# w.net
KiCad netlist of a schematic drawn in EAGLE
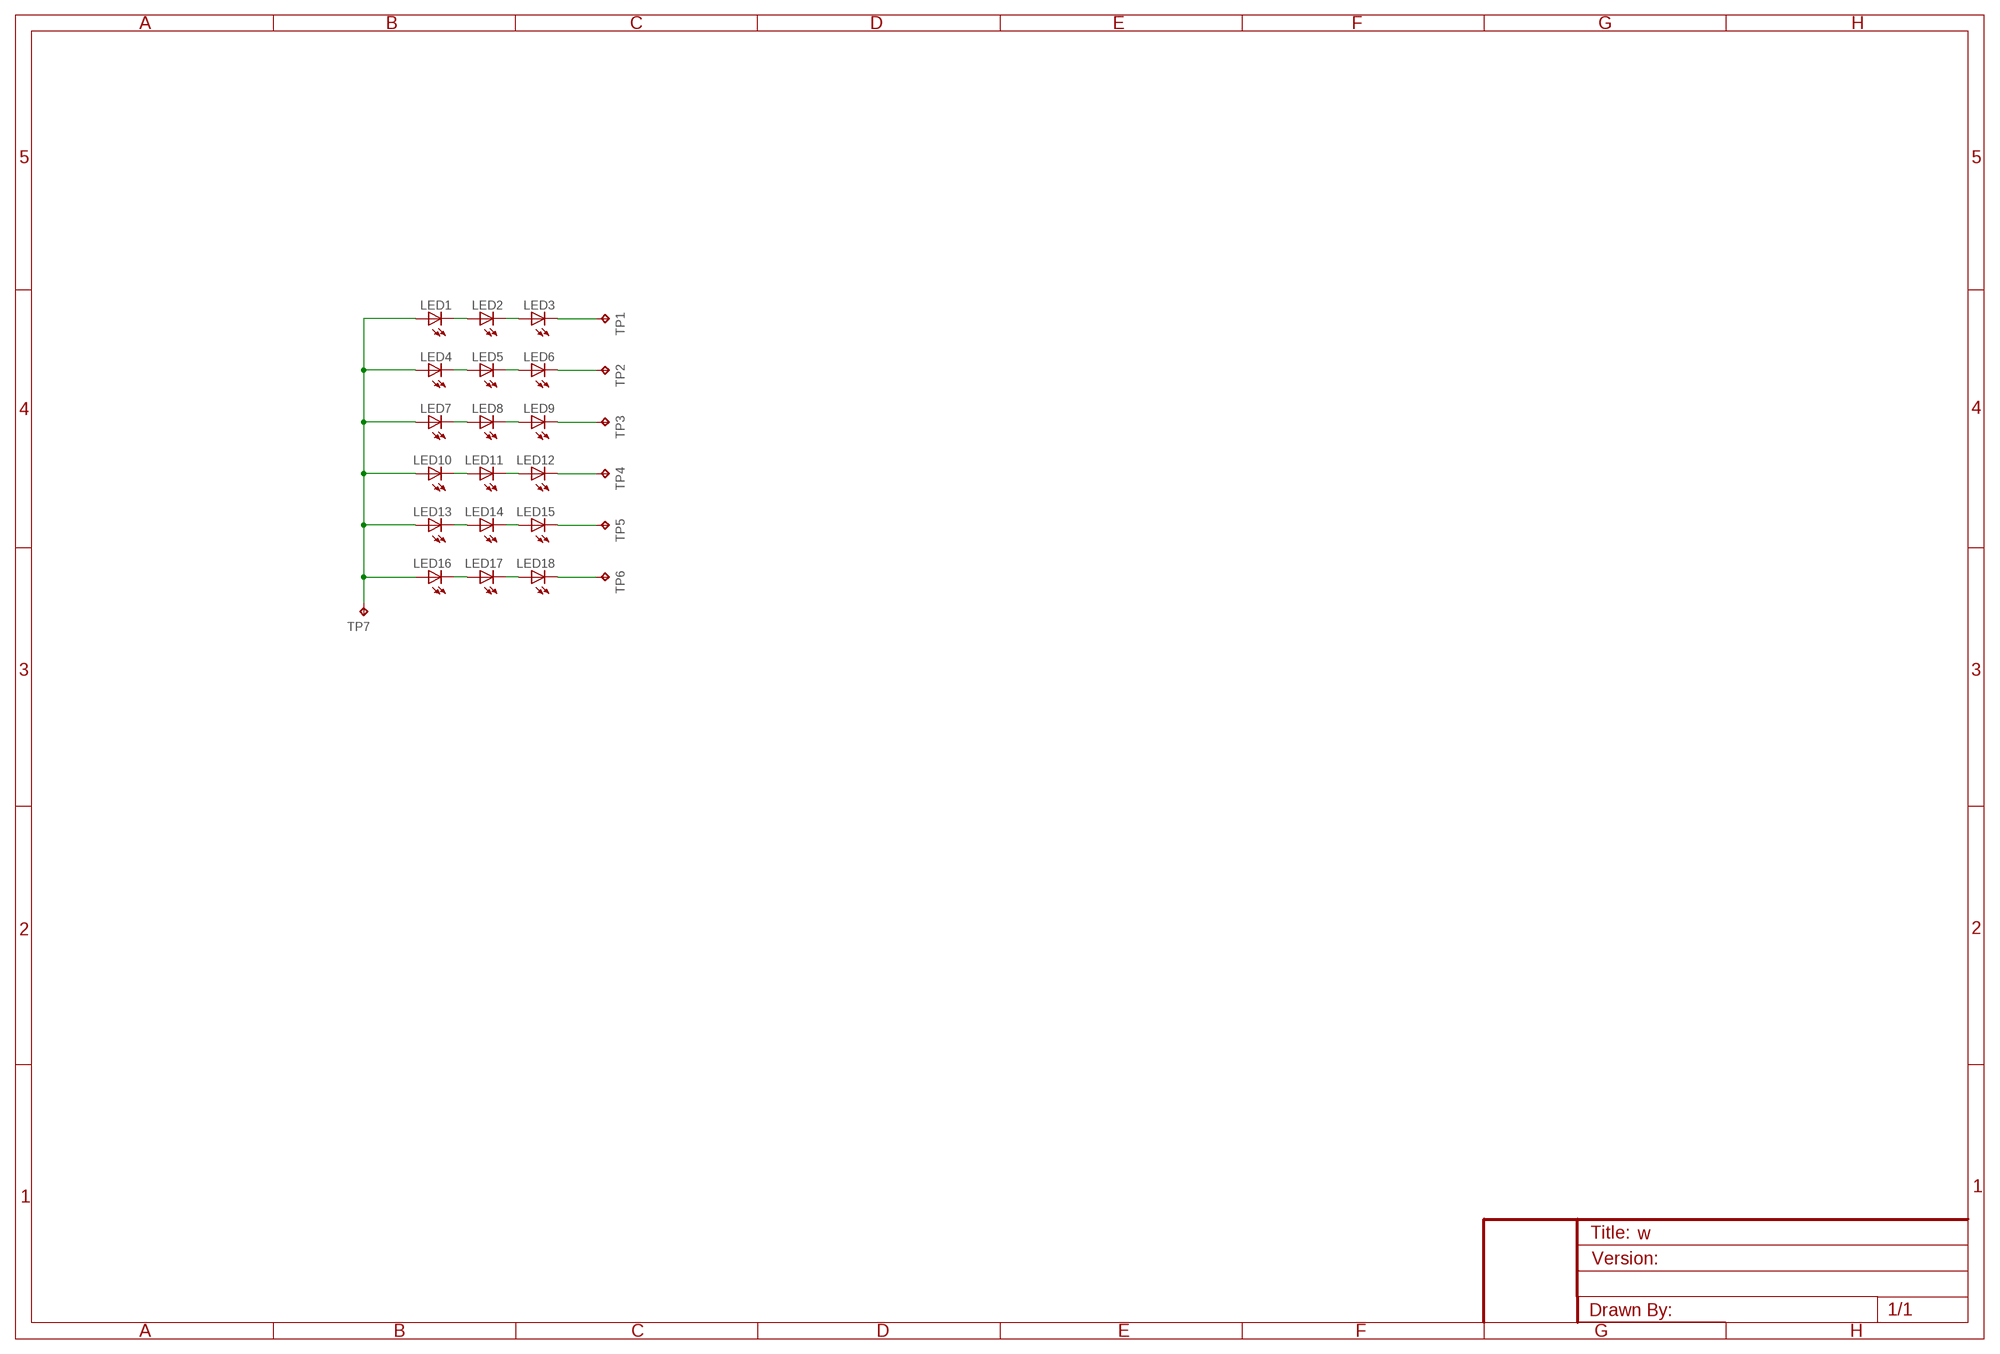
[diagram p0: schematic, sheet 1]

(export (version "E")
  (design (tool "Eeschema 10.0.6"))
  (components
    (comp (ref "LED1")
      (value "LED0805")
      (footprint "eagle-import:LED_0805")
      (libsource (lib "eagle-import") (part "LED0805"))
    )
    (comp (ref "LED2")
      (value "LED0805")
      (footprint "eagle-import:LED_0805")
      (libsource (lib "eagle-import") (part "LED0805"))
    )
    (comp (ref "LED3")
      (value "LED0805")
      (footprint "eagle-import:LED_0805")
      (libsource (lib "eagle-import") (part "LED0805"))
    )
    (comp (ref "LED4")
      (value "LED0805")
      (footprint "eagle-import:LED_0805")
      (libsource (lib "eagle-import") (part "LED0805"))
    )
    (comp (ref "LED5")
      (value "LED0805")
      (footprint "eagle-import:LED_0805")
      (libsource (lib "eagle-import") (part "LED0805"))
    )
    (comp (ref "LED6")
      (value "LED0805")
      (footprint "eagle-import:LED_0805")
      (libsource (lib "eagle-import") (part "LED0805"))
    )
    (comp (ref "LED7")
      (value "LED0805")
      (footprint "eagle-import:LED_0805")
      (libsource (lib "eagle-import") (part "LED0805"))
    )
    (comp (ref "LED8")
      (value "LED0805")
      (footprint "eagle-import:LED_0805")
      (libsource (lib "eagle-import") (part "LED0805"))
    )
    (comp (ref "LED9")
      (value "LED0805")
      (footprint "eagle-import:LED_0805")
      (libsource (lib "eagle-import") (part "LED0805"))
    )
    (comp (ref "LED10")
      (value "LED0805")
      (footprint "eagle-import:LED_0805")
      (libsource (lib "eagle-import") (part "LED0805"))
    )
    (comp (ref "LED11")
      (value "LED0805")
      (footprint "eagle-import:LED_0805")
      (libsource (lib "eagle-import") (part "LED0805"))
    )
    (comp (ref "LED12")
      (value "LED0805")
      (footprint "eagle-import:LED_0805")
      (libsource (lib "eagle-import") (part "LED0805"))
    )
    (comp (ref "LED13")
      (value "LED0805")
      (footprint "eagle-import:LED_0805")
      (libsource (lib "eagle-import") (part "LED0805"))
    )
    (comp (ref "LED14")
      (value "LED0805")
      (footprint "eagle-import:LED_0805")
      (libsource (lib "eagle-import") (part "LED0805"))
    )
    (comp (ref "LED15")
      (value "LED0805")
      (footprint "eagle-import:LED_0805")
      (libsource (lib "eagle-import") (part "LED0805"))
    )
    (comp (ref "LED16")
      (value "LED0805")
      (footprint "eagle-import:LED_0805")
      (libsource (lib "eagle-import") (part "LED0805"))
    )
    (comp (ref "LED17")
      (value "LED0805")
      (footprint "eagle-import:LED_0805")
      (libsource (lib "eagle-import") (part "LED0805"))
    )
    (comp (ref "LED18")
      (value "LED0805")
      (footprint "eagle-import:LED_0805")
      (libsource (lib "eagle-import") (part "LED0805"))
    )
    (comp (ref "TP1")
      (value "TEST_POINTPAD1-20")
      (footprint "eagle-import:P1-20")
      (libsource (lib "eagle-import") (part "TEST_POINTPAD1-20"))
    )
    (comp (ref "TP2")
      (value "TEST_POINTPAD1-20")
      (footprint "eagle-import:P1-20")
      (libsource (lib "eagle-import") (part "TEST_POINTPAD1-20"))
    )
    (comp (ref "TP3")
      (value "TEST_POINTPAD1-20")
      (footprint "eagle-import:P1-20")
      (libsource (lib "eagle-import") (part "TEST_POINTPAD1-20"))
    )
    (comp (ref "TP4")
      (value "TEST_POINTPAD1-20")
      (footprint "eagle-import:P1-20")
      (libsource (lib "eagle-import") (part "TEST_POINTPAD1-20"))
    )
    (comp (ref "TP5")
      (value "TEST_POINTPAD1-20")
      (footprint "eagle-import:P1-20")
      (libsource (lib "eagle-import") (part "TEST_POINTPAD1-20"))
    )
    (comp (ref "TP6")
      (value "TEST_POINTPAD1-20")
      (footprint "eagle-import:P1-20")
      (libsource (lib "eagle-import") (part "TEST_POINTPAD1-20"))
    )
    (comp (ref "TP7")
      (value "TEST_POINTPAD1-20")
      (footprint "eagle-import:P1-20")
      (libsource (lib "eagle-import") (part "TEST_POINTPAD1-20"))
    )
  )
  (nets
    (net (code "1") (name "Net-(LED1-PadA)") (class "Default")
      (node (ref "LED1") (pin "A") (pinfunction "A_A") (pintype "passive"))
      (node (ref "LED10") (pin "A") (pinfunction "A_A") (pintype "passive"))
      (node (ref "LED13") (pin "A") (pinfunction "A_A") (pintype "passive"))
      (node (ref "LED16") (pin "A") (pinfunction "A_A") (pintype "passive"))
      (node (ref "LED4") (pin "A") (pinfunction "A_A") (pintype "passive"))
      (node (ref "LED7") (pin "A") (pinfunction "A_A") (pintype "passive"))
      (node (ref "TP7") (pin "TP") (pinfunction "TP_TP") (pintype "input"))
    )
    (net (code "2") (name "Net-(LED1-PadC)") (class "Default")
      (node (ref "LED1") (pin "C") (pinfunction "C_C") (pintype "passive"))
      (node (ref "LED2") (pin "A") (pinfunction "A_A") (pintype "passive"))
    )
    (net (code "3") (name "Net-(LED2-PadC)") (class "Default")
      (node (ref "LED2") (pin "C") (pinfunction "C_C") (pintype "passive"))
      (node (ref "LED3") (pin "A") (pinfunction "A_A") (pintype "passive"))
    )
    (net (code "4") (name "Net-(LED3-PadC)") (class "Default")
      (node (ref "LED3") (pin "C") (pinfunction "C_C") (pintype "passive"))
      (node (ref "TP1") (pin "TP") (pinfunction "TP_TP") (pintype "input"))
    )
    (net (code "5") (name "Net-(LED4-PadC)") (class "Default")
      (node (ref "LED4") (pin "C") (pinfunction "C_C") (pintype "passive"))
      (node (ref "LED5") (pin "A") (pinfunction "A_A") (pintype "passive"))
    )
    (net (code "6") (name "Net-(LED5-PadC)") (class "Default")
      (node (ref "LED5") (pin "C") (pinfunction "C_C") (pintype "passive"))
      (node (ref "LED6") (pin "A") (pinfunction "A_A") (pintype "passive"))
    )
    (net (code "7") (name "Net-(LED6-PadC)") (class "Default")
      (node (ref "LED6") (pin "C") (pinfunction "C_C") (pintype "passive"))
      (node (ref "TP2") (pin "TP") (pinfunction "TP_TP") (pintype "input"))
    )
    (net (code "8") (name "Net-(LED7-PadC)") (class "Default")
      (node (ref "LED7") (pin "C") (pinfunction "C_C") (pintype "passive"))
      (node (ref "LED8") (pin "A") (pinfunction "A_A") (pintype "passive"))
    )
    (net (code "9") (name "Net-(LED8-PadC)") (class "Default")
      (node (ref "LED8") (pin "C") (pinfunction "C_C") (pintype "passive"))
      (node (ref "LED9") (pin "A") (pinfunction "A_A") (pintype "passive"))
    )
    (net (code "10") (name "Net-(LED9-PadC)") (class "Default")
      (node (ref "LED9") (pin "C") (pinfunction "C_C") (pintype "passive"))
      (node (ref "TP3") (pin "TP") (pinfunction "TP_TP") (pintype "input"))
    )
    (net (code "11") (name "Net-(LED10-PadC)") (class "Default")
      (node (ref "LED10") (pin "C") (pinfunction "C_C") (pintype "passive"))
      (node (ref "LED11") (pin "A") (pinfunction "A_A") (pintype "passive"))
    )
    (net (code "12") (name "Net-(LED11-PadC)") (class "Default")
      (node (ref "LED11") (pin "C") (pinfunction "C_C") (pintype "passive"))
      (node (ref "LED12") (pin "A") (pinfunction "A_A") (pintype "passive"))
    )
    (net (code "13") (name "Net-(LED12-PadC)") (class "Default")
      (node (ref "LED12") (pin "C") (pinfunction "C_C") (pintype "passive"))
      (node (ref "TP4") (pin "TP") (pinfunction "TP_TP") (pintype "input"))
    )
    (net (code "14") (name "Net-(LED13-PadC)") (class "Default")
      (node (ref "LED13") (pin "C") (pinfunction "C_C") (pintype "passive"))
      (node (ref "LED14") (pin "A") (pinfunction "A_A") (pintype "passive"))
    )
    (net (code "15") (name "Net-(LED14-PadC)") (class "Default")
      (node (ref "LED14") (pin "C") (pinfunction "C_C") (pintype "passive"))
      (node (ref "LED15") (pin "A") (pinfunction "A_A") (pintype "passive"))
    )
    (net (code "16") (name "Net-(LED15-PadC)") (class "Default")
      (node (ref "LED15") (pin "C") (pinfunction "C_C") (pintype "passive"))
      (node (ref "TP5") (pin "TP") (pinfunction "TP_TP") (pintype "input"))
    )
    (net (code "17") (name "Net-(LED16-PadC)") (class "Default")
      (node (ref "LED16") (pin "C") (pinfunction "C_C") (pintype "passive"))
      (node (ref "LED17") (pin "A") (pinfunction "A_A") (pintype "passive"))
    )
    (net (code "18") (name "Net-(LED17-PadC)") (class "Default")
      (node (ref "LED17") (pin "C") (pinfunction "C_C") (pintype "passive"))
      (node (ref "LED18") (pin "A") (pinfunction "A_A") (pintype "passive"))
    )
    (net (code "19") (name "Net-(LED18-PadC)") (class "Default")
      (node (ref "LED18") (pin "C") (pinfunction "C_C") (pintype "passive"))
      (node (ref "TP6") (pin "TP") (pinfunction "TP_TP") (pintype "input"))
    )
  )
)
